# esp32.net
KiCad netlist of a schematic drawn in EAGLE
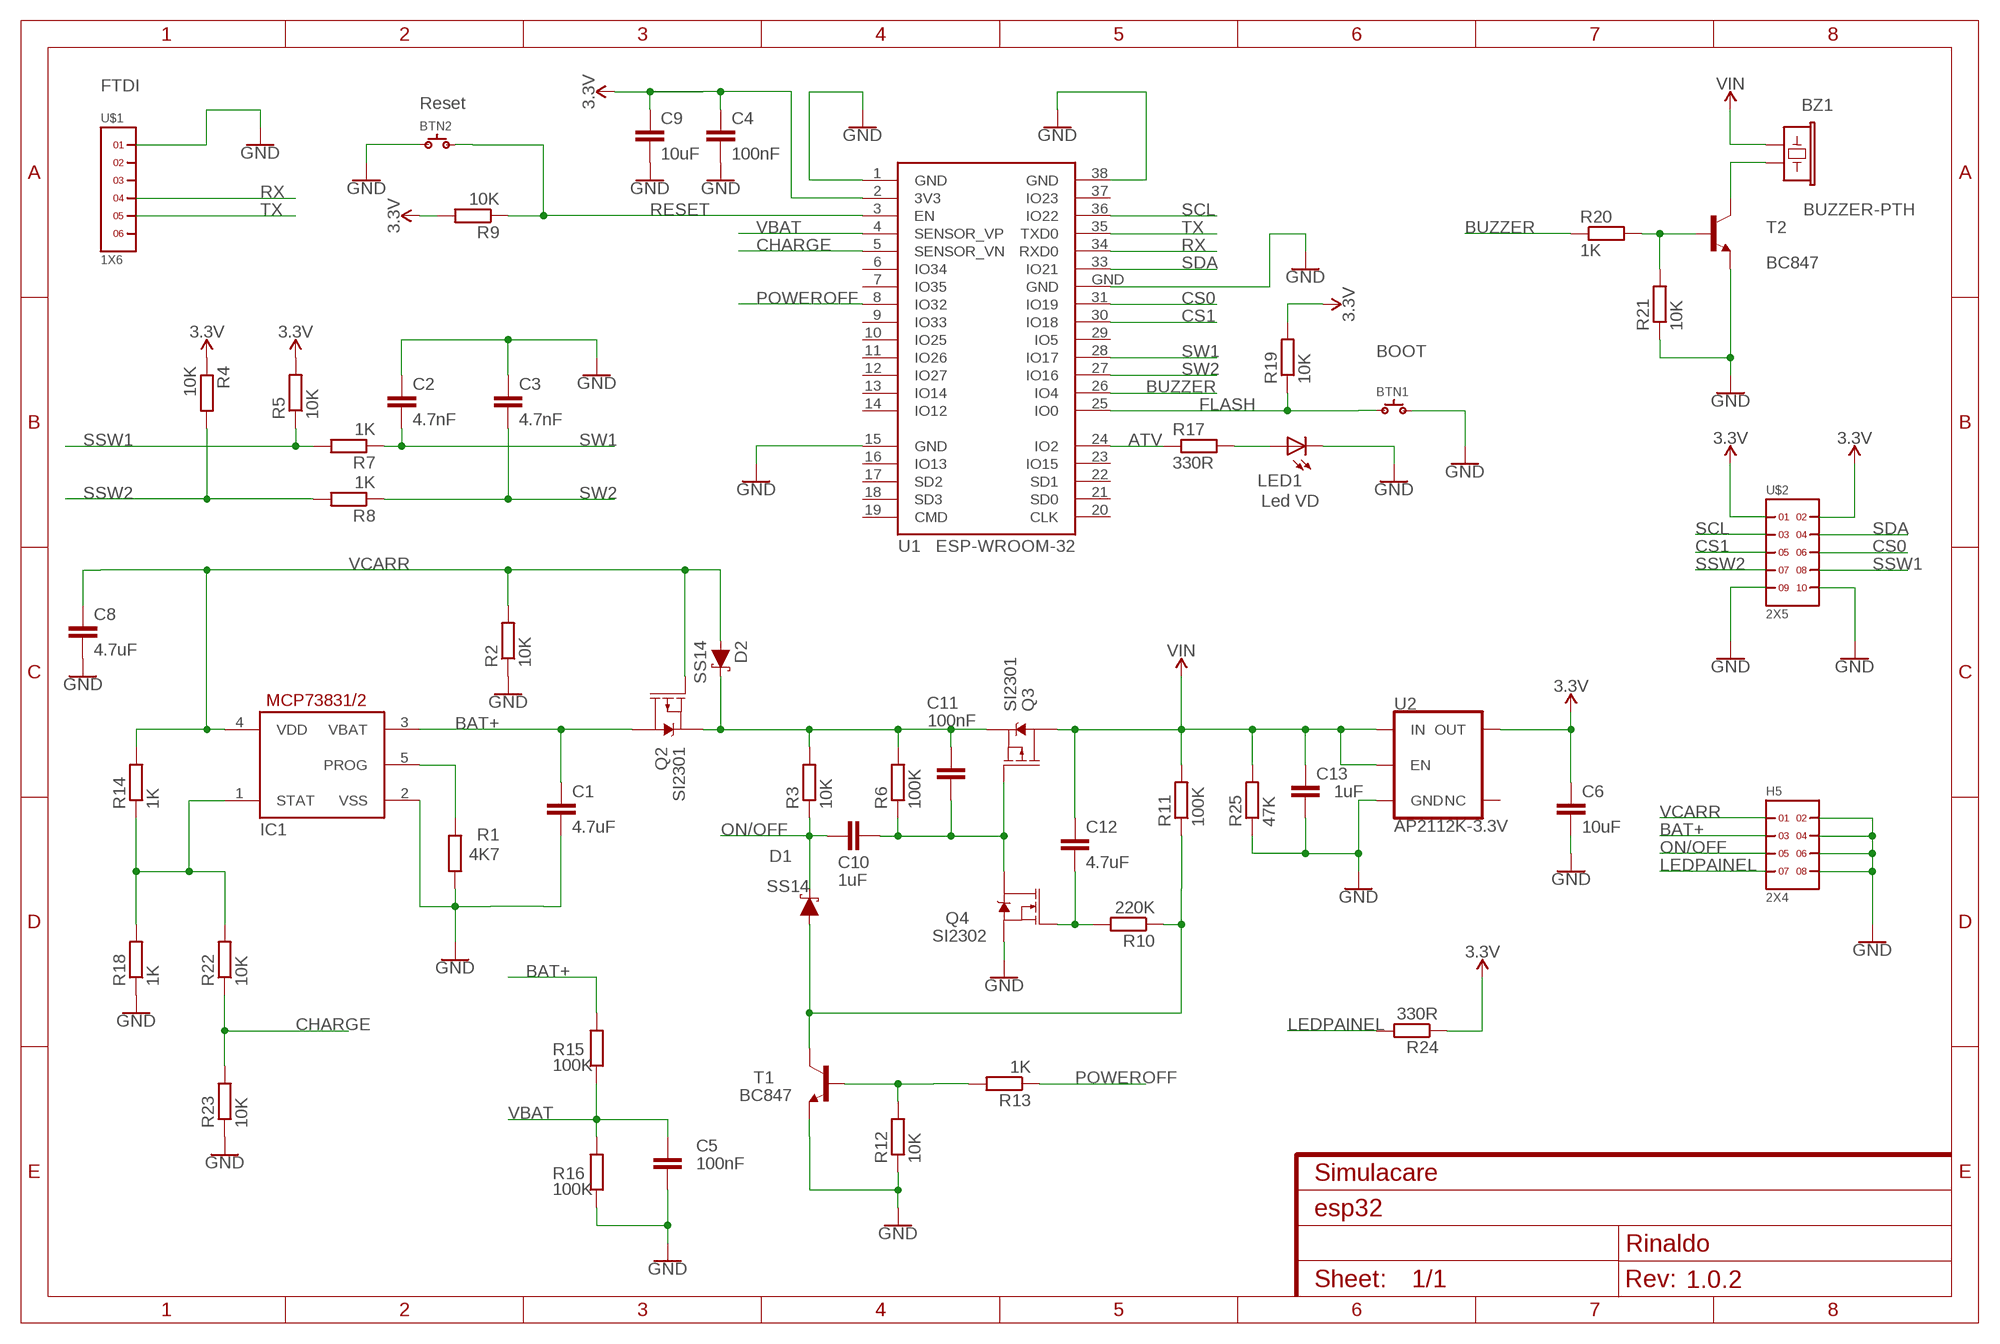
[diagram p0: schematic, sheet 1]

(export (version "E")
  (design (tool "Eeschema 10.0.6"))
  (components
    (comp (ref "BTN1")
      (value "SPST.B3U-1000P(M)")
      (footprint "eagle-import:B3U-1000P(M)")
      (libsource (lib "eagle-import") (part "SPST.B3U-1000P(M)"))
    )
    (comp (ref "BTN2")
      (value "SPST.B3U-1000P(M)")
      (footprint "eagle-import:B3U-1000P(M)")
      (libsource (lib "eagle-import") (part "SPST.B3U-1000P(M)"))
    )
    (comp (ref "BZ1")
      (value "BUZZER-PTH")
      (footprint "eagle-import:BUZZER-12MM")
      (libsource (lib "eagle-import") (part "BUZZER-PTH"))
    )
    (comp (ref "C1")
      (value "4.7uF")
      (footprint "eagle-import:C0603")
      (libsource (lib "eagle-import") (part "C-EUC0603"))
    )
    (comp (ref "C2")
      (value "4.7nF")
      (footprint "eagle-import:C0603")
      (libsource (lib "eagle-import") (part "C-EUC0603"))
    )
    (comp (ref "C3")
      (value "4.7nF")
      (footprint "eagle-import:C0603")
      (libsource (lib "eagle-import") (part "C-EUC0603"))
    )
    (comp (ref "C4")
      (value "100nF")
      (footprint "eagle-import:C0603")
      (libsource (lib "eagle-import") (part "C-EUC0603"))
    )
    (comp (ref "C5")
      (value "100nF")
      (footprint "eagle-import:C0603")
      (libsource (lib "eagle-import") (part "C-EUC0603"))
    )
    (comp (ref "C6")
      (value "10uF")
      (footprint "eagle-import:C0603")
      (libsource (lib "eagle-import") (part "C-EUC0603"))
    )
    (comp (ref "C8")
      (value "4.7uF")
      (footprint "eagle-import:C0603")
      (libsource (lib "eagle-import") (part "C-EUC0603"))
    )
    (comp (ref "C9")
      (value "10uF")
      (footprint "eagle-import:C0603")
      (libsource (lib "eagle-import") (part "C-EUC0603"))
    )
    (comp (ref "C10")
      (value "1uF")
      (footprint "eagle-import:C0603")
      (libsource (lib "eagle-import") (part "C-EUC0603"))
    )
    (comp (ref "C11")
      (value "100nF")
      (footprint "eagle-import:C0603")
      (libsource (lib "eagle-import") (part "C-EUC0603"))
    )
    (comp (ref "C12")
      (value "4.7uF")
      (footprint "eagle-import:C0603")
      (libsource (lib "eagle-import") (part "C-EUC0603"))
    )
    (comp (ref "C13")
      (value "1uF")
      (footprint "eagle-import:C0603")
      (libsource (lib "eagle-import") (part "C-EUC0603"))
    )
    (comp (ref "D1")
      (value "SS14")
      (footprint "eagle-import:SMA-DIODE")
      (libsource (lib "eagle-import") (part "DIODE-SCHOTTKY-SS14"))
    )
    (comp (ref "D2")
      (value "SS14")
      (footprint "eagle-import:SMA-DIODE")
      (libsource (lib "eagle-import") (part "DIODE-SCHOTTKY-SS14"))
    )
    (comp (ref "H5")
      (value "2X4")
      (footprint "eagle-import:2X4")
      (libsource (lib "eagle-import") (part "2X4"))
    )
    (comp (ref "IC1")
      (value "MCP73831/OT")
      (footprint "eagle-import:SOT23-5L")
      (libsource (lib "eagle-import") (part "MCP73831/OT"))
    )
    (comp (ref "LED1")
      (value "Led VD")
      (footprint "eagle-import:CHIP-LED0603")
      (libsource (lib "eagle-import") (part "LEDCHIP-LED0603"))
    )
    (comp (ref "Q2")
      (value "SI2301")
      (footprint "eagle-import:SOT23-3")
      (libsource (lib "eagle-import") (part "MOSFET_PCH-SI2309DS"))
    )
    (comp (ref "Q3")
      (value "SI2301")
      (footprint "eagle-import:SOT23-3")
      (libsource (lib "eagle-import") (part "MOSFET_PCH-SI2309DS"))
    )
    (comp (ref "Q4")
      (value "SI2302")
      (footprint "eagle-import:SOT23-3")
      (libsource (lib "eagle-import") (part "MOSFET-NCH-AO3404A"))
    )
    (comp (ref "R1")
      (value "4K7")
      (footprint "eagle-import:R0603")
      (libsource (lib "eagle-import") (part "R-EU_R0603"))
    )
    (comp (ref "R2")
      (value "10K")
      (footprint "eagle-import:R0603")
      (libsource (lib "eagle-import") (part "R-EU_R0603"))
    )
    (comp (ref "R3")
      (value "10K")
      (footprint "eagle-import:R0603")
      (libsource (lib "eagle-import") (part "R-EU_R0603"))
    )
    (comp (ref "R4")
      (value "10K")
      (footprint "eagle-import:R0603")
      (libsource (lib "eagle-import") (part "resistor_348_R-EU_R0603"))
    )
    (comp (ref "R5")
      (value "10K")
      (footprint "eagle-import:R0603")
      (libsource (lib "eagle-import") (part "resistor_348_R-EU_R0603"))
    )
    (comp (ref "R6")
      (value "100K")
      (footprint "eagle-import:R0603")
      (libsource (lib "eagle-import") (part "R-EU_R0603"))
    )
    (comp (ref "R7")
      (value "1K")
      (footprint "eagle-import:R0603")
      (libsource (lib "eagle-import") (part "resistor_348_R-EU_R0603"))
    )
    (comp (ref "R8")
      (value "1K")
      (footprint "eagle-import:R0603")
      (libsource (lib "eagle-import") (part "resistor_348_R-EU_R0603"))
    )
    (comp (ref "R9")
      (value "10K")
      (footprint "eagle-import:R0603")
      (libsource (lib "eagle-import") (part "resistor_348_R-EU_R0603"))
    )
    (comp (ref "R10")
      (value "220K")
      (footprint "eagle-import:R0603")
      (libsource (lib "eagle-import") (part "R-EU_R0603"))
    )
    (comp (ref "R11")
      (value "100K")
      (footprint "eagle-import:R0603")
      (libsource (lib "eagle-import") (part "R-EU_R0603"))
    )
    (comp (ref "R12")
      (value "10K")
      (footprint "eagle-import:R0603")
      (libsource (lib "eagle-import") (part "R-EU_R0603"))
    )
    (comp (ref "R13")
      (value "1K")
      (footprint "eagle-import:R0603")
      (libsource (lib "eagle-import") (part "R-EU_R0603"))
    )
    (comp (ref "R14")
      (value "1K")
      (footprint "eagle-import:R0603")
      (libsource (lib "eagle-import") (part "R-EU_R0603"))
    )
    (comp (ref "R15")
      (value "100K")
      (footprint "eagle-import:R0603")
      (libsource (lib "eagle-import") (part "resistor_348_R-EU_R0603"))
    )
    (comp (ref "R16")
      (value "100K")
      (footprint "eagle-import:R0603")
      (libsource (lib "eagle-import") (part "resistor_348_R-EU_R0603"))
    )
    (comp (ref "R17")
      (value "330R")
      (footprint "eagle-import:R0603")
      (libsource (lib "eagle-import") (part "resistor_348_R-EU_R0603"))
    )
    (comp (ref "R18")
      (value "1K")
      (footprint "eagle-import:R0603")
      (libsource (lib "eagle-import") (part "R-EU_R0603"))
    )
    (comp (ref "R19")
      (value "10K")
      (footprint "eagle-import:R0603")
      (libsource (lib "eagle-import") (part "resistor_348_R-EU_R0603"))
    )
    (comp (ref "R20")
      (value "1K")
      (footprint "eagle-import:R0603")
      (libsource (lib "eagle-import") (part "resistor_348_R-EU_R0603"))
    )
    (comp (ref "R21")
      (value "10K")
      (footprint "eagle-import:R0603")
      (libsource (lib "eagle-import") (part "resistor_348_R-EU_R0603"))
    )
    (comp (ref "R22")
      (value "10K")
      (footprint "eagle-import:R0603")
      (libsource (lib "eagle-import") (part "R-EU_R0603"))
    )
    (comp (ref "R23")
      (value "10K")
      (footprint "eagle-import:R0603")
      (libsource (lib "eagle-import") (part "R-EU_R0603"))
    )
    (comp (ref "R24")
      (value "330R")
      (footprint "eagle-import:R0603")
      (libsource (lib "eagle-import") (part "resistor_348_R-EU_R0603"))
    )
    (comp (ref "R25")
      (value "47K")
      (footprint "eagle-import:R0603")
      (libsource (lib "eagle-import") (part "R-EU_R0603"))
    )
    (comp (ref "T1")
      (value "BC847")
      (footprint "eagle-import:SOT23")
      (libsource (lib "eagle-import") (part "BC847"))
    )
    (comp (ref "T2")
      (value "BC847")
      (footprint "eagle-import:SOT23")
      (libsource (lib "eagle-import") (part "BC847"))
    )
    (comp (ref "U$1")
      (value "1X6")
      (footprint "eagle-import:1X6")
      (libsource (lib "eagle-import") (part "1X6"))
    )
    (comp (ref "U$2")
      (value "2X5")
      (footprint "eagle-import:2X5")
      (libsource (lib "eagle-import") (part "2X5"))
    )
    (comp (ref "U1")
      (value "ESP-WROOM-32")
      (footprint "eagle-import:ESP-WROOM-32")
      (libsource (lib "eagle-import") (part "ESP-WROOM-32"))
    )
    (comp (ref "U2")
      (value "AP2112K-3.3V")
      (footprint "eagle-import:SOT23-5")
      (libsource (lib "eagle-import") (part "V_REG_AP2112K-3.3V"))
    )
  )
  (nets
    (net (code "1") (name "/ATV") (class "Default")
      (node (ref "R17") (pin "1") (pinfunction "1_1") (pintype "passive"))
      (node (ref "U1") (pin "24") (pinfunction "IO2_24") (pintype "bidirectional"))
    )
    (net (code "2") (name "/BAT+") (class "Default")
      (node (ref "C1") (pin "1") (pinfunction "1_1") (pintype "passive"))
      (node (ref "H5") (pin "3") (pinfunction "3_3") (pintype "bidirectional"))
      (node (ref "IC1") (pin "3") (pinfunction "VBAT_3") (pintype "bidirectional"))
      (node (ref "Q2") (pin "3") (pinfunction "D_3") (pintype "bidirectional"))
      (node (ref "R15") (pin "2") (pinfunction "2_2") (pintype "passive"))
    )
    (net (code "3") (name "/BUZZER") (class "Default")
      (node (ref "R20") (pin "1") (pinfunction "1_1") (pintype "passive"))
      (node (ref "U1") (pin "26") (pinfunction "IO4_26") (pintype "bidirectional"))
    )
    (net (code "4") (name "/CHARGE") (class "Default")
      (node (ref "R22") (pin "1") (pinfunction "1_1") (pintype "passive"))
      (node (ref "R23") (pin "2") (pinfunction "2_2") (pintype "passive"))
      (node (ref "U1") (pin "5") (pinfunction "SENSOR_VN_5") (pintype "bidirectional"))
    )
    (net (code "5") (name "/CS0") (class "Default")
      (node (ref "U$2") (pin "6") (pinfunction "6_6") (pintype "bidirectional"))
      (node (ref "U1") (pin "31") (pinfunction "IO19_31") (pintype "bidirectional"))
    )
    (net (code "6") (name "/CS1") (class "Default")
      (node (ref "U$2") (pin "5") (pinfunction "5_5") (pintype "bidirectional"))
      (node (ref "U1") (pin "30") (pinfunction "IO18_30") (pintype "bidirectional"))
    )
    (net (code "7") (name "/FLASH") (class "Default")
      (node (ref "BTN1") (pin "1") (pinfunction "1_1") (pintype "bidirectional"))
      (node (ref "R19") (pin "1") (pinfunction "1_1") (pintype "passive"))
      (node (ref "U1") (pin "25") (pinfunction "IO0_25") (pintype "bidirectional"))
    )
    (net (code "8") (name "/LEDPAINEL") (class "Default")
      (node (ref "H5") (pin "7") (pinfunction "7_7") (pintype "bidirectional"))
      (node (ref "R24") (pin "2") (pinfunction "2_2") (pintype "passive"))
    )
    (net (code "9") (name "/ON{slash}OFF") (class "Default")
      (node (ref "C10") (pin "1") (pinfunction "1_1") (pintype "passive"))
      (node (ref "D1") (pin "C") (pinfunction "C_C") (pintype "passive"))
      (node (ref "H5") (pin "5") (pinfunction "5_5") (pintype "bidirectional"))
      (node (ref "R3") (pin "1") (pinfunction "1_1") (pintype "passive"))
    )
    (net (code "10") (name "/POWEROFF") (class "Default")
      (node (ref "R13") (pin "1") (pinfunction "1_1") (pintype "passive"))
      (node (ref "U1") (pin "8") (pinfunction "IO32_8") (pintype "bidirectional"))
    )
    (net (code "11") (name "/RESET") (class "Default")
      (node (ref "BTN2") (pin "2") (pinfunction "2_2") (pintype "bidirectional"))
      (node (ref "R9") (pin "1") (pinfunction "1_1") (pintype "passive"))
      (node (ref "U1") (pin "3") (pinfunction "EN_3") (pintype "input"))
    )
    (net (code "12") (name "/RX") (class "Default")
      (node (ref "U$1") (pin "4") (pinfunction "4_4") (pintype "bidirectional"))
      (node (ref "U1") (pin "34") (pinfunction "RXD0_34") (pintype "bidirectional"))
    )
    (net (code "13") (name "/SCL") (class "Default")
      (node (ref "U$2") (pin "3") (pinfunction "3_3") (pintype "bidirectional"))
      (node (ref "U1") (pin "36") (pinfunction "IO22_36") (pintype "bidirectional"))
    )
    (net (code "14") (name "/SDA") (class "Default")
      (node (ref "U$2") (pin "4") (pinfunction "4_4") (pintype "bidirectional"))
      (node (ref "U1") (pin "33") (pinfunction "IO21_33") (pintype "bidirectional"))
    )
    (net (code "15") (name "/SSW1") (class "Default")
      (node (ref "R5") (pin "1") (pinfunction "1_1") (pintype "passive"))
      (node (ref "R7") (pin "2") (pinfunction "2_2") (pintype "passive"))
      (node (ref "U$2") (pin "8") (pinfunction "8_8") (pintype "bidirectional"))
    )
    (net (code "16") (name "/SSW2") (class "Default")
      (node (ref "R4") (pin "2") (pinfunction "2_2") (pintype "passive"))
      (node (ref "R8") (pin "2") (pinfunction "2_2") (pintype "passive"))
      (node (ref "U$2") (pin "7") (pinfunction "7_7") (pintype "bidirectional"))
    )
    (net (code "17") (name "/SW1") (class "Default")
      (node (ref "C2") (pin "2") (pinfunction "2_2") (pintype "passive"))
      (node (ref "R7") (pin "1") (pinfunction "1_1") (pintype "passive"))
      (node (ref "U1") (pin "28") (pinfunction "IO17_28") (pintype "bidirectional"))
    )
    (net (code "18") (name "/SW2") (class "Default")
      (node (ref "C3") (pin "2") (pinfunction "2_2") (pintype "passive"))
      (node (ref "R8") (pin "1") (pinfunction "1_1") (pintype "passive"))
      (node (ref "U1") (pin "27") (pinfunction "IO16_27") (pintype "bidirectional"))
    )
    (net (code "19") (name "/TX") (class "Default")
      (node (ref "U$1") (pin "5") (pinfunction "5_5") (pintype "bidirectional"))
      (node (ref "U1") (pin "35") (pinfunction "TXD0_35") (pintype "bidirectional"))
    )
    (net (code "20") (name "/VBAT") (class "Default")
      (node (ref "C5") (pin "1") (pinfunction "1_1") (pintype "passive"))
      (node (ref "R15") (pin "1") (pinfunction "1_1") (pintype "passive"))
      (node (ref "R16") (pin "2") (pinfunction "2_2") (pintype "passive"))
      (node (ref "U1") (pin "4") (pinfunction "SENSOR_VP_4") (pintype "bidirectional"))
    )
    (net (code "21") (name "/VCARR") (class "Default")
      (node (ref "C8") (pin "1") (pinfunction "1_1") (pintype "passive"))
      (node (ref "D2") (pin "A") (pinfunction "A_A") (pintype "passive"))
      (node (ref "H5") (pin "1") (pinfunction "1_1") (pintype "bidirectional"))
      (node (ref "IC1") (pin "4") (pinfunction "VDD_4") (pintype "power_in"))
      (node (ref "Q2") (pin "1") (pinfunction "G_1") (pintype "bidirectional"))
      (node (ref "R14") (pin "2") (pinfunction "2_2") (pintype "passive"))
      (node (ref "R2") (pin "2") (pinfunction "2_2") (pintype "passive"))
    )
    (net (code "22") (name "3.3V") (class "Default")
      (node (ref "C4") (pin "1") (pinfunction "1_1") (pintype "passive"))
      (node (ref "C6") (pin "1") (pinfunction "1_1") (pintype "passive"))
      (node (ref "C9") (pin "1") (pinfunction "1_1") (pintype "passive"))
      (node (ref "R19") (pin "2") (pinfunction "2_2") (pintype "passive"))
      (node (ref "R24") (pin "1") (pinfunction "1_1") (pintype "passive"))
      (node (ref "R4") (pin "1") (pinfunction "1_1") (pintype "passive"))
      (node (ref "R5") (pin "2") (pinfunction "2_2") (pintype "passive"))
      (node (ref "R9") (pin "2") (pinfunction "2_2") (pintype "passive"))
      (node (ref "U$2") (pin "1") (pinfunction "1_1") (pintype "bidirectional"))
      (node (ref "U$2") (pin "2") (pinfunction "2_2") (pintype "bidirectional"))
      (node (ref "U1") (pin "2") (pinfunction "3V3_2") (pintype "power_in"))
      (node (ref "U2") (pin "5") (pinfunction "OUT_5") (pintype "passive"))
    )
    (net (code "23") (name "GND") (class "Default")
      (node (ref "BTN1") (pin "2") (pinfunction "2_2") (pintype "bidirectional"))
      (node (ref "BTN2") (pin "1") (pinfunction "1_1") (pintype "bidirectional"))
      (node (ref "C1") (pin "2") (pinfunction "2_2") (pintype "passive"))
      (node (ref "C13") (pin "2") (pinfunction "2_2") (pintype "passive"))
      (node (ref "C2") (pin "1") (pinfunction "1_1") (pintype "passive"))
      (node (ref "C3") (pin "1") (pinfunction "1_1") (pintype "passive"))
      (node (ref "C4") (pin "2") (pinfunction "2_2") (pintype "passive"))
      (node (ref "C5") (pin "2") (pinfunction "2_2") (pintype "passive"))
      (node (ref "C6") (pin "2") (pinfunction "2_2") (pintype "passive"))
      (node (ref "C8") (pin "2") (pinfunction "2_2") (pintype "passive"))
      (node (ref "C9") (pin "2") (pinfunction "2_2") (pintype "passive"))
      (node (ref "H5") (pin "2") (pinfunction "2_2") (pintype "bidirectional"))
      (node (ref "H5") (pin "4") (pinfunction "4_4") (pintype "bidirectional"))
      (node (ref "H5") (pin "6") (pinfunction "6_6") (pintype "bidirectional"))
      (node (ref "H5") (pin "8") (pinfunction "8_8") (pintype "bidirectional"))
      (node (ref "IC1") (pin "2") (pinfunction "VSS_2") (pintype "power_in"))
      (node (ref "LED1") (pin "C") (pinfunction "C_C") (pintype "passive"))
      (node (ref "Q4") (pin "2") (pinfunction "S_2") (pintype "bidirectional"))
      (node (ref "R1") (pin "1") (pinfunction "1_1") (pintype "passive"))
      (node (ref "R12") (pin "1") (pinfunction "1_1") (pintype "passive"))
      (node (ref "R16") (pin "1") (pinfunction "1_1") (pintype "passive"))
      (node (ref "R18") (pin "1") (pinfunction "1_1") (pintype "passive"))
      (node (ref "R2") (pin "1") (pinfunction "1_1") (pintype "passive"))
      (node (ref "R21") (pin "1") (pinfunction "1_1") (pintype "passive"))
      (node (ref "R23") (pin "1") (pinfunction "1_1") (pintype "passive"))
      (node (ref "R25") (pin "1") (pinfunction "1_1") (pintype "passive"))
      (node (ref "T1") (pin "2") (pinfunction "E_2") (pintype "passive"))
      (node (ref "T2") (pin "2") (pinfunction "E_2") (pintype "passive"))
      (node (ref "U$1") (pin "1") (pinfunction "1_1") (pintype "bidirectional"))
      (node (ref "U$2") (pin "10") (pinfunction "10_10") (pintype "bidirectional"))
      (node (ref "U$2") (pin "9") (pinfunction "9_9") (pintype "bidirectional"))
      (node (ref "U1") (pin "1") (pinfunction "GND_1") (pintype "power_in"))
      (node (ref "U1") (pin "15") (pinfunction "GND_15") (pintype "power_in"))
      (node (ref "U1") (pin "38") (pinfunction "GND_38") (pintype "power_in"))
      (node (ref "U1") (pin "GND") (pinfunction "GND_GND") (pintype "power_in"))
      (node (ref "U2") (pin "2") (pinfunction "GND_2") (pintype "input"))
    )
    (net (code "24") (name "Net-(BZ1-2)") (class "Default")
      (node (ref "BZ1") (pin "-") (pinfunction "2_-") (pintype "passive"))
      (node (ref "T2") (pin "3") (pinfunction "C_3") (pintype "passive"))
    )
    (net (code "25") (name "Net-(IC1-PROG)") (class "Default")
      (node (ref "IC1") (pin "5") (pinfunction "PROG_5") (pintype "input"))
      (node (ref "R1") (pin "2") (pinfunction "2_2") (pintype "passive"))
    )
    (net (code "26") (name "Net-(IC1-STAT)") (class "Default")
      (node (ref "IC1") (pin "1") (pinfunction "STAT_1") (pintype "output"))
      (node (ref "R14") (pin "1") (pinfunction "1_1") (pintype "passive"))
      (node (ref "R18") (pin "2") (pinfunction "2_2") (pintype "passive"))
      (node (ref "R22") (pin "2") (pinfunction "2_2") (pintype "passive"))
    )
    (net (code "27") (name "Net-(LED1-PadA)") (class "Default")
      (node (ref "LED1") (pin "A") (pinfunction "A_A") (pintype "passive"))
      (node (ref "R17") (pin "2") (pinfunction "2_2") (pintype "passive"))
    )
    (net (code "28") (name "Net-(Q2-S)") (class "Default")
      (node (ref "C11") (pin "2") (pinfunction "2_2") (pintype "passive"))
      (node (ref "D2") (pin "C") (pinfunction "C_C") (pintype "passive"))
      (node (ref "Q2") (pin "2") (pinfunction "S_2") (pintype "bidirectional"))
      (node (ref "Q3") (pin "2") (pinfunction "S_2") (pintype "bidirectional"))
      (node (ref "R3") (pin "2") (pinfunction "2_2") (pintype "passive"))
      (node (ref "R6") (pin "2") (pinfunction "2_2") (pintype "passive"))
    )
    (net (code "29") (name "Net-(Q3-G)") (class "Default")
      (node (ref "C10") (pin "2") (pinfunction "2_2") (pintype "passive"))
      (node (ref "C11") (pin "1") (pinfunction "1_1") (pintype "passive"))
      (node (ref "Q3") (pin "1") (pinfunction "G_1") (pintype "bidirectional"))
      (node (ref "Q4") (pin "3") (pinfunction "D_3") (pintype "bidirectional"))
      (node (ref "R6") (pin "1") (pinfunction "1_1") (pintype "passive"))
    )
    (net (code "30") (name "Net-(Q4-G)") (class "Default")
      (node (ref "C12") (pin "2") (pinfunction "2_2") (pintype "passive"))
      (node (ref "Q4") (pin "1") (pinfunction "G_1") (pintype "bidirectional"))
      (node (ref "R10") (pin "2") (pinfunction "2_2") (pintype "passive"))
    )
    (net (code "31") (name "Net-(T1-B)") (class "Default")
      (node (ref "R12") (pin "2") (pinfunction "2_2") (pintype "passive"))
      (node (ref "R13") (pin "2") (pinfunction "2_2") (pintype "passive"))
      (node (ref "T1") (pin "1") (pinfunction "B_1") (pintype "passive"))
    )
    (net (code "32") (name "Net-(T1-C)") (class "Default")
      (node (ref "D1") (pin "A") (pinfunction "A_A") (pintype "passive"))
      (node (ref "R10") (pin "1") (pinfunction "1_1") (pintype "passive"))
      (node (ref "R11") (pin "1") (pinfunction "1_1") (pintype "passive"))
      (node (ref "T1") (pin "3") (pinfunction "C_3") (pintype "passive"))
    )
    (net (code "33") (name "Net-(T2-B)") (class "Default")
      (node (ref "R20") (pin "2") (pinfunction "2_2") (pintype "passive"))
      (node (ref "R21") (pin "2") (pinfunction "2_2") (pintype "passive"))
      (node (ref "T2") (pin "1") (pinfunction "B_1") (pintype "passive"))
    )
    (net (code "34") (name "VIN") (class "Default")
      (node (ref "BZ1") (pin "+") (pinfunction "1_+") (pintype "passive"))
      (node (ref "C12") (pin "1") (pinfunction "1_1") (pintype "passive"))
      (node (ref "C13") (pin "1") (pinfunction "1_1") (pintype "passive"))
      (node (ref "Q3") (pin "3") (pinfunction "D_3") (pintype "bidirectional"))
      (node (ref "R11") (pin "2") (pinfunction "2_2") (pintype "passive"))
      (node (ref "R25") (pin "2") (pinfunction "2_2") (pintype "passive"))
      (node (ref "U2") (pin "1") (pinfunction "IN_1") (pintype "input"))
      (node (ref "U2") (pin "3") (pinfunction "EN_3") (pintype "input"))
    )
    (net (code "35") (name "unconnected-(U$1-Pad2)") (class "Default")
      (node (ref "U$1") (pin "2") (pinfunction "2_2") (pintype "bidirectional"))
    )
    (net (code "36") (name "unconnected-(U$1-Pad3)") (class "Default")
      (node (ref "U$1") (pin "3") (pinfunction "3_3") (pintype "bidirectional"))
    )
    (net (code "37") (name "unconnected-(U$1-Pad6)") (class "Default")
      (node (ref "U$1") (pin "6") (pinfunction "6_6") (pintype "bidirectional"))
    )
    (net (code "38") (name "unconnected-(U1-CLK-Pad20)") (class "Default")
      (node (ref "U1") (pin "20") (pinfunction "CLK_20") (pintype "bidirectional"))
    )
    (net (code "39") (name "unconnected-(U1-CMD-Pad19)") (class "Default")
      (node (ref "U1") (pin "19") (pinfunction "CMD_19") (pintype "bidirectional"))
    )
    (net (code "40") (name "unconnected-(U1-IO5-Pad29)") (class "Default")
      (node (ref "U1") (pin "29") (pinfunction "IO5_29") (pintype "bidirectional"))
    )
    (net (code "41") (name "unconnected-(U1-IO12-Pad14)") (class "Default")
      (node (ref "U1") (pin "14") (pinfunction "IO12_14") (pintype "bidirectional"))
    )
    (net (code "42") (name "unconnected-(U1-IO13-Pad16)") (class "Default")
      (node (ref "U1") (pin "16") (pinfunction "IO13_16") (pintype "bidirectional"))
    )
    (net (code "43") (name "unconnected-(U1-IO14-Pad13)") (class "Default")
      (node (ref "U1") (pin "13") (pinfunction "IO14_13") (pintype "bidirectional"))
    )
    (net (code "44") (name "unconnected-(U1-IO15-Pad23)") (class "Default")
      (node (ref "U1") (pin "23") (pinfunction "IO15_23") (pintype "bidirectional"))
    )
    (net (code "45") (name "unconnected-(U1-IO23-Pad37)") (class "Default")
      (node (ref "U1") (pin "37") (pinfunction "IO23_37") (pintype "bidirectional"))
    )
    (net (code "46") (name "unconnected-(U1-IO25-Pad10)") (class "Default")
      (node (ref "U1") (pin "10") (pinfunction "IO25_10") (pintype "bidirectional"))
    )
    (net (code "47") (name "unconnected-(U1-IO26-Pad11)") (class "Default")
      (node (ref "U1") (pin "11") (pinfunction "IO26_11") (pintype "bidirectional"))
    )
    (net (code "48") (name "unconnected-(U1-IO27-Pad12)") (class "Default")
      (node (ref "U1") (pin "12") (pinfunction "IO27_12") (pintype "bidirectional"))
    )
    (net (code "49") (name "unconnected-(U1-IO33-Pad9)") (class "Default")
      (node (ref "U1") (pin "9") (pinfunction "IO33_9") (pintype "bidirectional"))
    )
    (net (code "50") (name "unconnected-(U1-IO34-Pad6)") (class "Default")
      (node (ref "U1") (pin "6") (pinfunction "IO34_6") (pintype "bidirectional"))
    )
    (net (code "51") (name "unconnected-(U1-IO35-Pad7)") (class "Default")
      (node (ref "U1") (pin "7") (pinfunction "IO35_7") (pintype "bidirectional"))
    )
    (net (code "52") (name "unconnected-(U1-SD0-Pad21)") (class "Default")
      (node (ref "U1") (pin "21") (pinfunction "SD0_21") (pintype "bidirectional"))
    )
    (net (code "53") (name "unconnected-(U1-SD1-Pad22)") (class "Default")
      (node (ref "U1") (pin "22") (pinfunction "SD1_22") (pintype "bidirectional"))
    )
    (net (code "54") (name "unconnected-(U1-SD2-Pad17)") (class "Default")
      (node (ref "U1") (pin "17") (pinfunction "SD2_17") (pintype "bidirectional"))
    )
    (net (code "55") (name "unconnected-(U1-SD3-Pad18)") (class "Default")
      (node (ref "U1") (pin "18") (pinfunction "SD3_18") (pintype "bidirectional"))
    )
    (net (code "56") (name "unconnected-(U2-NC-Pad4)") (class "Default")
      (node (ref "U2") (pin "4") (pinfunction "NC_4") (pintype "no_connect"))
    )
  )
)
